# Output_-_24V.net
KiCad netlist of a schematic drawn in Altium Designer
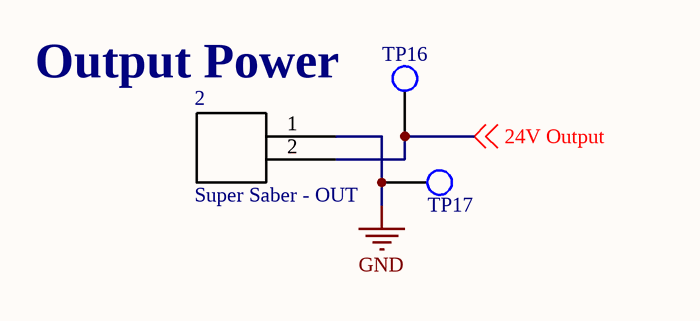
[diagram p0: Output - 24V.SchDoc]

(export (version "E")
  (design (tool "Eeschema 10.0.6"))
  (components
    (comp (ref "2")
      (value "Super Saber - OUT")
      (footprint "0431600102")
      (libsource (lib "Connector Schematic Symbols") (part "Super Saber"))
    )
    (comp (ref "TP16")
      (value "Test Point")
      (footprint "Test Point Through-hole")
      (libsource (lib "Test Points") (part "Test Point"))
    )
    (comp (ref "TP17")
      (value "Test Point")
      (footprint "Test Point Through-hole")
      (libsource (lib "Test Points") (part "Test Point"))
    )
  )
  (nets
    (net (code "1") (name "24V Output") (class "Default")
      (node (ref "2") (pin "2") (pintype "passive"))
      (node (ref "TP16") (pin "1") (pinfunction "1_1") (pintype "passive"))
    )
    (net (code "2") (name "GND") (class "Default")
      (node (ref "2") (pin "1") (pintype "passive"))
      (node (ref "TP17") (pin "1") (pinfunction "1_1") (pintype "passive"))
    )
  )
)
